# 2A_Buck_Boost.net
KiCad netlist of a schematic drawn in EAGLE
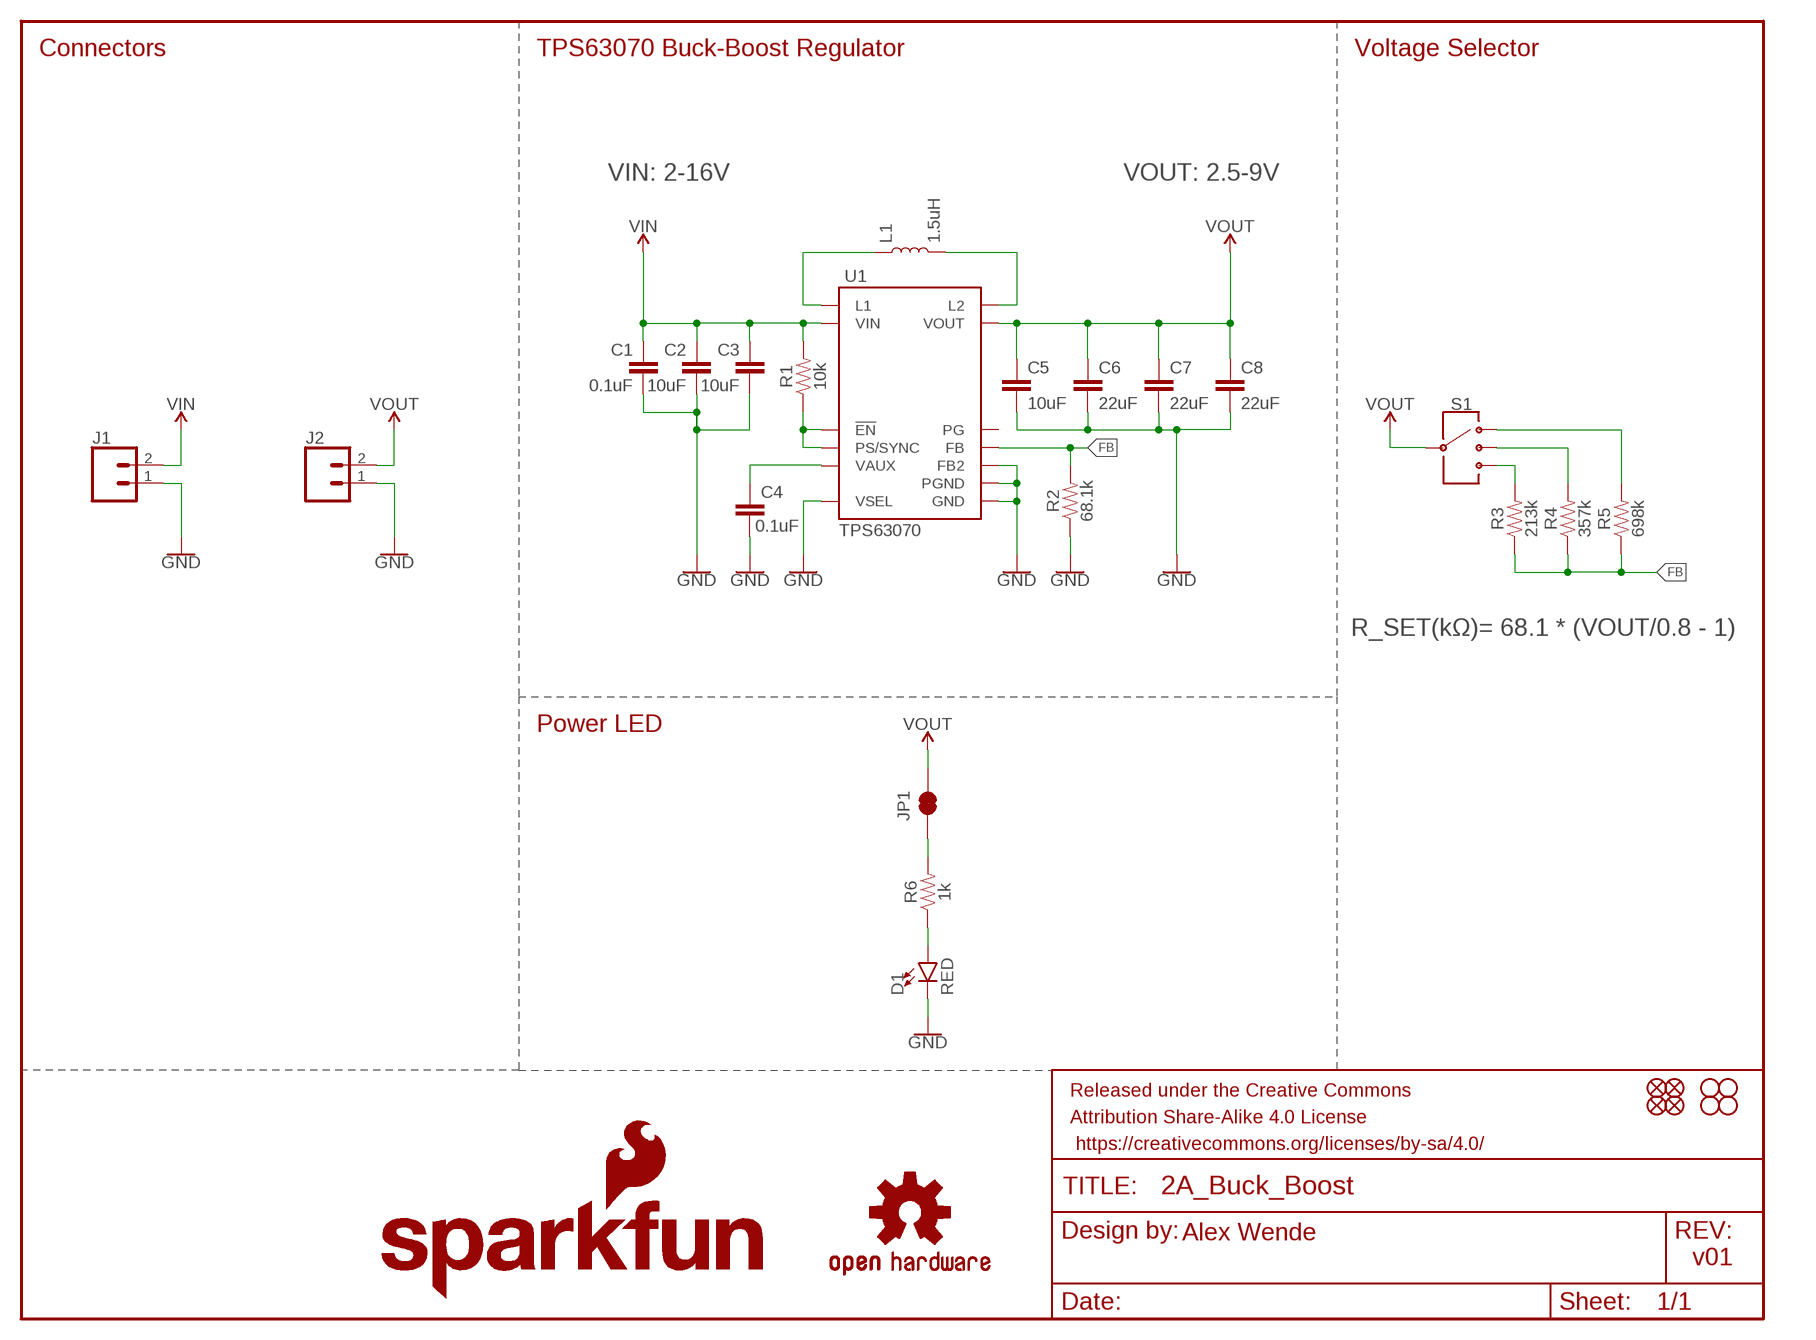
[diagram p0: schematic, sheet 1]

(export (version "E")
  (design (tool "Eeschema 10.0.6"))
  (components
    (comp (ref "C1")
      (value "0.1uF")
      (footprint "eagle-import:0603")
      (libsource (lib "eagle-import") (part "0.1UF-0603-25V-(+80/-20%)"))
    )
    (comp (ref "C2")
      (value "10uF")
      (footprint "eagle-import:0805")
      (libsource (lib "eagle-import") (part "10UF-0805-25V-10%"))
    )
    (comp (ref "C3")
      (value "10uF")
      (footprint "eagle-import:0805")
      (libsource (lib "eagle-import") (part "10UF-0805-25V-10%"))
    )
    (comp (ref "C4")
      (value "0.1uF")
      (footprint "eagle-import:0603")
      (libsource (lib "eagle-import") (part "0.1UF-0603-25V-(+80/-20%)"))
    )
    (comp (ref "C5")
      (value "10uF")
      (footprint "eagle-import:0805")
      (libsource (lib "eagle-import") (part "10UF-0805-25V-10%"))
    )
    (comp (ref "C6")
      (value "22uF")
      (footprint "eagle-import:0805")
      (libsource (lib "eagle-import") (part "22UF-0805-16V-20%"))
    )
    (comp (ref "C7")
      (value "22uF")
      (footprint "eagle-import:0805")
      (libsource (lib "eagle-import") (part "22UF-0805-16V-20%"))
    )
    (comp (ref "C8")
      (value "22uF")
      (footprint "eagle-import:0805")
      (libsource (lib "eagle-import") (part "22UF-0805-16V-20%"))
    )
    (comp (ref "D1")
      (value "RED")
      (footprint "eagle-import:LED-0603")
      (libsource (lib "eagle-import") (part "LED-RED0603"))
    )
    (comp (ref "FD1")
      (value "FIDUCIAL1X2")
      (footprint "eagle-import:FIDUCIAL-1X2")
      (libsource (lib "eagle-import") (part "FIDUCIAL1X2"))
    )
    (comp (ref "FD2")
      (value "FIDUCIAL1X2")
      (footprint "eagle-import:FIDUCIAL-1X2")
      (libsource (lib "eagle-import") (part "FIDUCIAL1X2"))
    )
    (comp (ref "FD3")
      (value "FIDUCIAL1X2")
      (footprint "eagle-import:FIDUCIAL-1X2")
      (libsource (lib "eagle-import") (part "FIDUCIAL1X2"))
    )
    (comp (ref "FD4")
      (value "FIDUCIAL1X2")
      (footprint "eagle-import:FIDUCIAL-1X2")
      (libsource (lib "eagle-import") (part "FIDUCIAL1X2"))
    )
    (comp (ref "FRAME1")
      (value "FRAME-LETTER")
      (footprint "eagle-import:CREATIVE_COMMONS")
      (libsource (lib "eagle-import") (part "FRAME-LETTER"))
    )
    (comp (ref "H1")
      (value "STAND-OFF")
      (footprint "eagle-import:STAND-OFF")
      (libsource (lib "eagle-import") (part "STAND-OFF"))
    )
    (comp (ref "H2")
      (value "STAND-OFF")
      (footprint "eagle-import:STAND-OFF")
      (libsource (lib "eagle-import") (part "STAND-OFF"))
    )
    (comp (ref "H3")
      (value "STAND-OFF")
      (footprint "eagle-import:STAND-OFF")
      (libsource (lib "eagle-import") (part "STAND-OFF"))
    )
    (comp (ref "H4")
      (value "STAND-OFF")
      (footprint "eagle-import:STAND-OFF")
      (libsource (lib "eagle-import") (part "STAND-OFF"))
    )
    (comp (ref "J1")
      (value "CONN_021X02_NO_SILK")
      (footprint "eagle-import:1X02_NO_SILK")
      (libsource (lib "eagle-import") (part "CONN_021X02_NO_SILK"))
    )
    (comp (ref "J2")
      (value "CONN_021X02_NO_SILK")
      (footprint "eagle-import:1X02_NO_SILK")
      (libsource (lib "eagle-import") (part "CONN_021X02_NO_SILK"))
    )
    (comp (ref "JP1")
      (value "JUMPER-SMT_2_NC_TRACE_NO-SILK")
      (footprint "eagle-import:SMT-JUMPER_2_NC_TRACE_NO-SILK")
      (libsource (lib "eagle-import") (part "JUMPER-SMT_2_NC_TRACE_NO-SILK"))
    )
    (comp (ref "L1")
      (value "1.5uH")
      (footprint "eagle-import:XFL4020")
      (libsource (lib "eagle-import") (part "INDUCTOR-XFL40201.5UH"))
    )
    (comp (ref "LOGO1")
      (value "SFE_LOGO_NAME_FLAME.1_INCH")
      (footprint "eagle-import:SFE_LOGO_NAME_FLAME_.1")
      (libsource (lib "eagle-import") (part "SFE_LOGO_NAME_FLAME.1_INCH"))
    )
    (comp (ref "LOGO2")
      (value "OSHW-LOGOS")
      (footprint "eagle-import:OSHW-LOGO-S")
      (libsource (lib "eagle-import") (part "OSHW-LOGOS"))
    )
    (comp (ref "R1")
      (value "10k")
      (footprint "eagle-import:0603")
      (libsource (lib "eagle-import") (part "10KOHM-0603-1/10W-1%"))
    )
    (comp (ref "R2")
      (value "68.1k")
      (footprint "eagle-import:0603")
      (libsource (lib "eagle-import") (part "68.1KOHM-0603-1/10W-1%"))
    )
    (comp (ref "R3")
      (value "213k")
      (footprint "eagle-import:0603")
      (libsource (lib "eagle-import") (part "213KOHM"))
    )
    (comp (ref "R4")
      (value "357k")
      (footprint "eagle-import:0603")
      (libsource (lib "eagle-import") (part "357KOHM"))
    )
    (comp (ref "R5")
      (value "698k")
      (footprint "eagle-import:0603")
      (libsource (lib "eagle-import") (part "698KOHM"))
    )
    (comp (ref "R6")
      (value "1k")
      (footprint "eagle-import:0603")
      (libsource (lib "eagle-import") (part "1KOHM-0603-1/10W-1%"))
    )
    (comp (ref "S1")
      (value "SWITCH-SP3T-SMD")
      (footprint "eagle-import:SWITCH_SP3T_SMD")
      (libsource (lib "eagle-import") (part "SWITCH-SP3T-SMD"))
    )
    (comp (ref "U1")
      (value "TPS63070")
      (footprint "eagle-import:VQFN-15-HR(3X2.5)")
      (libsource (lib "eagle-import") (part "TPS63070"))
    )
  )
  (nets
    (net (code "1") (name "FB") (class "Default")
      (node (ref "R2") (pin "2") (pinfunction "2_2") (pintype "passive"))
      (node (ref "R3") (pin "1") (pinfunction "1_1") (pintype "passive"))
      (node (ref "R4") (pin "1") (pinfunction "1_1") (pintype "passive"))
      (node (ref "R5") (pin "1") (pinfunction "1_1") (pintype "passive"))
      (node (ref "U1") (pin "P$5") (pinfunction "FB_P$5") (pintype "bidirectional"))
    )
    (net (code "2") (name "GND") (class "Default")
      (node (ref "C1") (pin "2") (pinfunction "2_2") (pintype "passive"))
      (node (ref "C2") (pin "2") (pinfunction "2_2") (pintype "passive"))
      (node (ref "C3") (pin "2") (pinfunction "2_2") (pintype "passive"))
      (node (ref "C4") (pin "2") (pinfunction "2_2") (pintype "passive"))
      (node (ref "C5") (pin "2") (pinfunction "2_2") (pintype "passive"))
      (node (ref "C6") (pin "2") (pinfunction "2_2") (pintype "passive"))
      (node (ref "C7") (pin "2") (pinfunction "2_2") (pintype "passive"))
      (node (ref "C8") (pin "2") (pinfunction "2_2") (pintype "passive"))
      (node (ref "D1") (pin "C") (pinfunction "C_C") (pintype "passive"))
      (node (ref "J1") (pin "1") (pinfunction "1_1") (pintype "passive"))
      (node (ref "J2") (pin "1") (pinfunction "1_1") (pintype "passive"))
      (node (ref "R2") (pin "1") (pinfunction "1_1") (pintype "passive"))
      (node (ref "U1") (pin "P$10") (pinfunction "PGND_P$10") (pintype "bidirectional"))
      (node (ref "U1") (pin "P$15") (pinfunction "VSEL_P$15") (pintype "bidirectional"))
      (node (ref "U1") (pin "P$4") (pinfunction "GND_P$4") (pintype "bidirectional"))
      (node (ref "U1") (pin "P$6") (pinfunction "FB2_P$6") (pintype "bidirectional"))
    )
    (net (code "3") (name "Net-(D1-PadA)") (class "Default")
      (node (ref "D1") (pin "A") (pinfunction "A_A") (pintype "passive"))
      (node (ref "R6") (pin "1") (pinfunction "1_1") (pintype "passive"))
    )
    (net (code "4") (name "Net-(JP1-Pad1)") (class "Default")
      (node (ref "JP1") (pin "1") (pinfunction "1_1") (pintype "passive"))
      (node (ref "R6") (pin "2") (pinfunction "2_2") (pintype "passive"))
    )
    (net (code "5") (name "Net-(L1-1)") (class "Default")
      (node (ref "L1") (pin "P$1") (pinfunction "1_P$1") (pintype "passive"))
      (node (ref "U1") (pin "P$11") (pinfunction "L1_P$11") (pintype "bidirectional"))
    )
    (net (code "6") (name "Net-(L1-2)") (class "Default")
      (node (ref "L1") (pin "P$2") (pinfunction "2_P$2") (pintype "passive"))
      (node (ref "U1") (pin "P$9") (pinfunction "L2_P$9") (pintype "bidirectional"))
    )
    (net (code "7") (name "Net-(R3-Pad2)") (class "Default")
      (node (ref "R3") (pin "2") (pinfunction "2_2") (pintype "passive"))
      (node (ref "S1") (pin "4") (pinfunction "4_4") (pintype "bidirectional"))
    )
    (net (code "8") (name "Net-(R4-Pad2)") (class "Default")
      (node (ref "R4") (pin "2") (pinfunction "2_2") (pintype "passive"))
      (node (ref "S1") (pin "2") (pinfunction "2_2") (pintype "bidirectional"))
    )
    (net (code "9") (name "Net-(R5-Pad2)") (class "Default")
      (node (ref "R5") (pin "2") (pinfunction "2_2") (pintype "passive"))
      (node (ref "S1") (pin "1") (pinfunction "1_1") (pintype "bidirectional"))
    )
    (net (code "10") (name "Net-(U1-PS{slash}SYNC)") (class "Default")
      (node (ref "R1") (pin "1") (pinfunction "1_1") (pintype "passive"))
      (node (ref "U1") (pin "P$1") (pinfunction "PS/SYNC_P$1") (pintype "bidirectional"))
      (node (ref "U1") (pin "P$14") (pinfunction "~{EN}_P$14") (pintype "bidirectional"))
    )
    (net (code "11") (name "Net-(U1-VAUX)") (class "Default")
      (node (ref "C4") (pin "1") (pinfunction "1_1") (pintype "passive"))
      (node (ref "U1") (pin "P$3") (pinfunction "VAUX_P$3") (pintype "bidirectional"))
    )
    (net (code "12") (name "VIN") (class "Default")
      (node (ref "C1") (pin "1") (pinfunction "1_1") (pintype "passive"))
      (node (ref "C2") (pin "1") (pinfunction "1_1") (pintype "passive"))
      (node (ref "C3") (pin "1") (pinfunction "1_1") (pintype "passive"))
      (node (ref "J1") (pin "2") (pinfunction "2_2") (pintype "passive"))
      (node (ref "R1") (pin "2") (pinfunction "2_2") (pintype "passive"))
      (node (ref "U1") (pin "P$12/13") (pinfunction "VIN_P$12/13") (pintype "bidirectional"))
    )
    (net (code "13") (name "VOUT") (class "Default")
      (node (ref "C5") (pin "1") (pinfunction "1_1") (pintype "passive"))
      (node (ref "C6") (pin "1") (pinfunction "1_1") (pintype "passive"))
      (node (ref "C7") (pin "1") (pinfunction "1_1") (pintype "passive"))
      (node (ref "C8") (pin "1") (pinfunction "1_1") (pintype "passive"))
      (node (ref "J2") (pin "2") (pinfunction "2_2") (pintype "passive"))
      (node (ref "JP1") (pin "2") (pinfunction "2_2") (pintype "passive"))
      (node (ref "S1") (pin "3") (pinfunction "3_3") (pintype "bidirectional"))
      (node (ref "U1") (pin "P$7/8") (pinfunction "VOUT_P$7/8") (pintype "bidirectional"))
    )
    (net (code "14") (name "unconnected-(U1-PG-PadP$2)") (class "Default")
      (node (ref "U1") (pin "P$2") (pinfunction "PG_P$2") (pintype "bidirectional"))
    )
  )
)
